# double_amp.net
KiCad netlist of a schematic drawn in Altium Designer
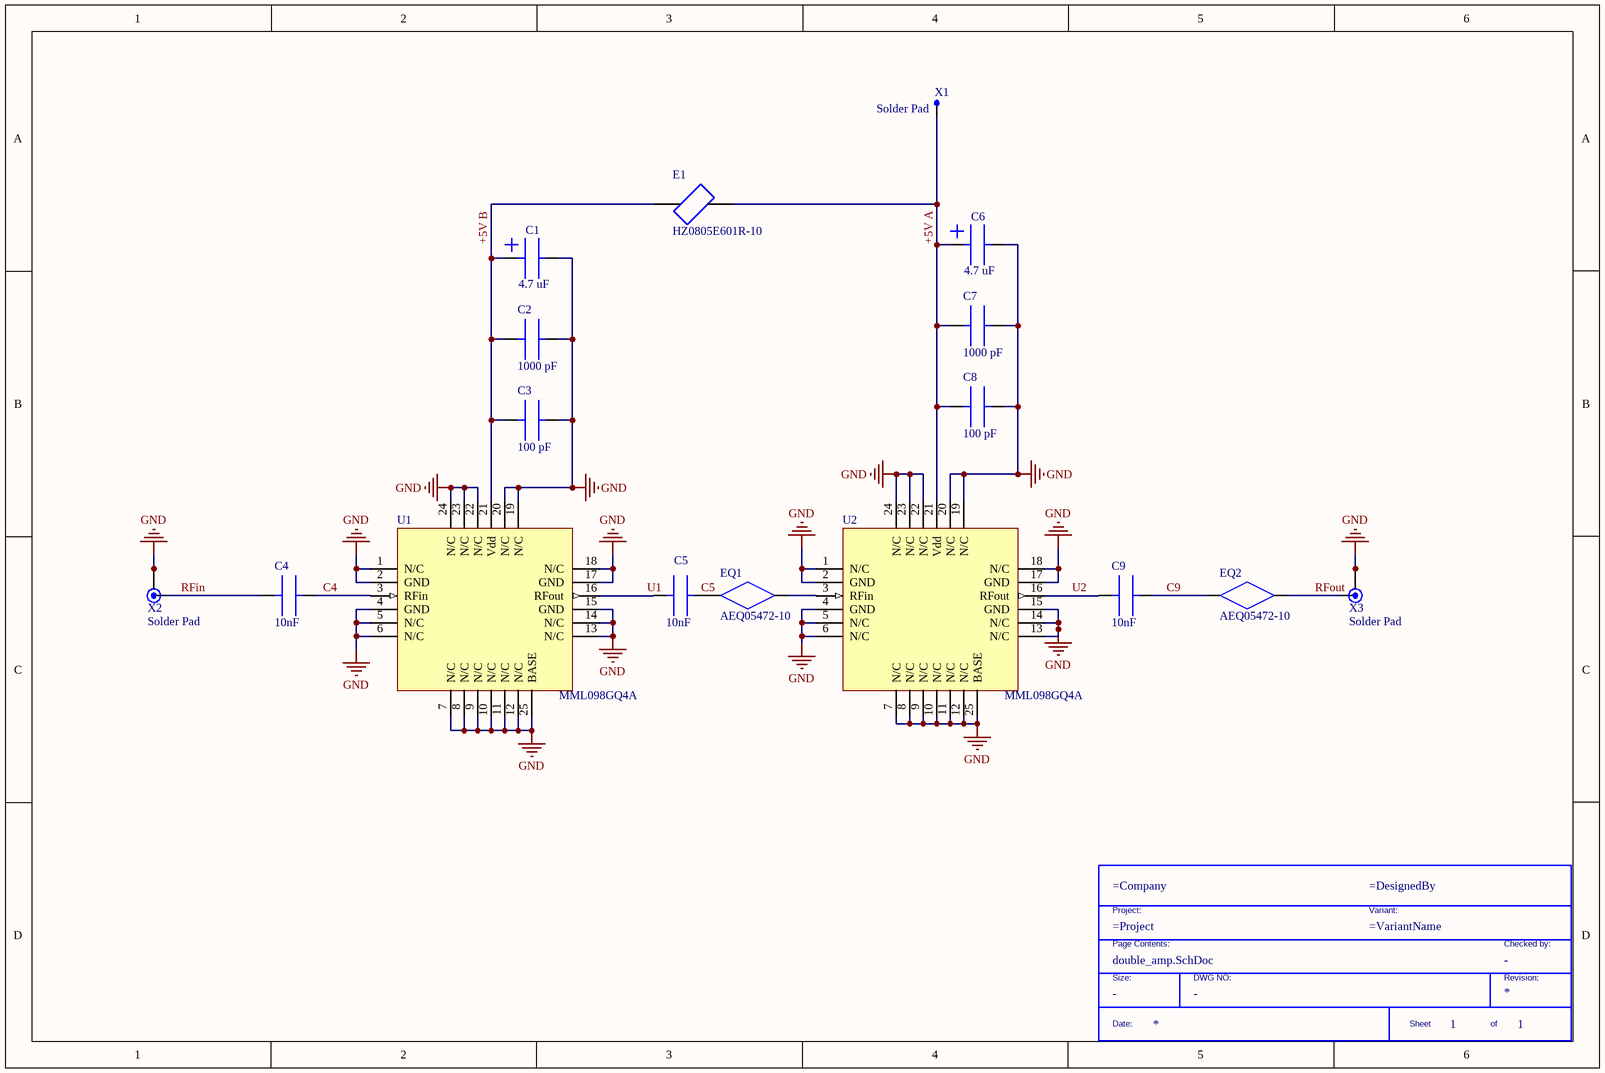
[diagram p0: double_amp.SchDoc]

(export (version "E")
  (design (tool "Eeschema 10.0.6"))
  (components
    (comp (ref "*")
      (value "TitleBlock")
      (description "Standard Title Block")
      (fields (field (name "DWG NO") "-") (field (name "SIZE") "-") (field (name "CHECKED BY") "-"))
      (libsource (lib "amp") (part "TitleBlock"))
    )
    (comp (ref "C1")
      (value "4.7 uF")
      (footprint "C4_7uF")
      (fields
        (field (name "MANUFACTURER") "Vishay Sprague")
        (field (name "MANUFACTURER PART NUMBER") "TH3A475K010C2900")
      )
      (libsource (lib "amp") (part "C7_4uF_TH3A475K010C2900"))
    )
    (comp (ref "C2")
      (value "1000 pF")
      (footprint "C1000pF__C100nF")
      (fields
        (field (name "MANUFACTURER") "Murata")
        (field (name "MANUFACTURER PART NUMBER") "GCM1885C1H102FA16D")
      )
      (libsource (lib "amp") (part "C1000pF_GCM1885C1H102FA16D"))
    )
    (comp (ref "C3")
      (value "100 pF")
      (footprint "C100pF")
      (description "Multilayer Ceramic Capacitors MLCC - SMD/SMT 100 pF 100 VDC 1% 0402 C0G (NP0)")
      (fields
        (field (name "MANUFACTURER") "Murata")
        (field (name "MANUFACTURER PART NUMBER") "GRM1555C2A101FA01D")
      )
      (libsource (lib "amp") (part "C100pF_GRM1555C2A101FA01D"))
    )
    (comp (ref "C4")
      (value "10nF")
      (footprint "C10nF")
      (fields (field (name "MANUFACTURER") "Murata") (field (name "MANUFACTURER PART NUMBER") "939113733510"))
      (libsource (lib "amp") (part "C10nF_939113733510"))
    )
    (comp (ref "C5")
      (value "10nF")
      (footprint "C10nF")
      (fields (field (name "MANUFACTURER") "Murata") (field (name "MANUFACTURER PART NUMBER") "939113733510"))
      (libsource (lib "amp") (part "C10nF_939113733510"))
    )
    (comp (ref "C6")
      (value "4.7 uF")
      (footprint "C4_7uF")
      (fields
        (field (name "MANUFACTURER") "Vishay Sprague")
        (field (name "MANUFACTURER PART NUMBER") "TH3A475K010C2900")
      )
      (libsource (lib "amp") (part "C7_4uF_TH3A475K010C2900"))
    )
    (comp (ref "C7")
      (value "1000 pF")
      (footprint "C1000pF__C100nF")
      (fields
        (field (name "MANUFACTURER") "Murata")
        (field (name "MANUFACTURER PART NUMBER") "GCM1885C1H102FA16D")
      )
      (libsource (lib "amp") (part "C1000pF_GCM1885C1H102FA16D"))
    )
    (comp (ref "C8")
      (value "100 pF")
      (footprint "C100pF")
      (description "Multilayer Ceramic Capacitors MLCC - SMD/SMT 100 pF 100 VDC 1% 0402 C0G (NP0)")
      (fields
        (field (name "MANUFACTURER") "Murata")
        (field (name "MANUFACTURER PART NUMBER") "GRM1555C2A101FA01D")
      )
      (libsource (lib "amp") (part "C100pF_GRM1555C2A101FA01D"))
    )
    (comp (ref "C9")
      (value "10nF")
      (footprint "C10nF")
      (fields (field (name "MANUFACTURER") "Murata") (field (name "MANUFACTURER PART NUMBER") "939113733510"))
      (libsource (lib "amp") (part "C10nF_939113733510"))
    )
    (comp (ref "E1")
      (value "HZ0805E601R-10")
      (footprint "FB_HZ0805E601R-10")
      (fields (field (name "MF") "Laird-Signal Integrity Products"))
      (libsource (lib "HZ0805E601R-10") (part "HZ0805E601R-10"))
    )
    (comp (ref "EQ1")
      (value "AEQ05472-10")
      (footprint "EQ_AEQ05472")
      (description "Rf Filter Gain Equalizer 2SMD")
      (fields (field (name "MANUFACTURER") "Knowles Dielectric Labs"))
      (libsource (lib "amp") (part "EQ_AEQ05472-10"))
    )
    (comp (ref "EQ2")
      (value "AEQ05472-10")
      (footprint "EQ_AEQ05472")
      (description "Rf Filter Gain Equalizer 2SMD")
      (fields (field (name "MANUFACTURER") "Knowles Dielectric Labs"))
      (libsource (lib "amp") (part "EQ_AEQ05472-10"))
    )
    (comp (ref "U1")
      (value "MML098GQ4A")
      (footprint "amp_MML098GQ4A")
      (libsource (lib "amp") (part "amp_MML098GQ4A"))
    )
    (comp (ref "U2")
      (value "MML098GQ4A")
      (footprint "amp_MML098GQ4A")
      (libsource (lib "amp") (part "amp_MML098GQ4A"))
    )
    (comp (ref "X1")
      (value "Solder Pad")
      (footprint "Solder Pad")
      (description "Pad to solder wires to")
      (libsource (lib "amp") (part "Solder Pad"))
    )
    (comp (ref "X2")
      (value "Solder Pad")
      (footprint "CPW Edge Connector")
      (description "Solder pad for RF Coplanar Waveguide Rogers 4350B Thickness 0.020\" Copper 1oz")
      (libsource (lib "amp") (part "RF  CPW Solder Pad"))
    )
    (comp (ref "X3")
      (value "Solder Pad")
      (footprint "CPW Edge Connector")
      (description "Solder pad for RF Coplanar Waveguide Rogers 4350B Thickness 0.020\" Copper 1oz")
      (libsource (lib "amp") (part "RF  CPW Solder Pad"))
    )
  )
  (nets
    (net (code "1") (name "/+5V A") (class "Default")
      (node (ref "C6") (pin "1") (pinfunction "+_1") (pintype "passive"))
      (node (ref "C7") (pin "1") (pinfunction "1_1") (pintype "passive"))
      (node (ref "C8") (pin "1") (pinfunction "1_1") (pintype "passive"))
      (node (ref "E1") (pin "2") (pinfunction "2_2") (pintype "passive"))
      (node (ref "U2") (pin "21") (pinfunction "Vdd_21") (pintype "power_in"))
      (node (ref "X1") (pin "1") (pinfunction "1_1") (pintype "passive"))
    )
    (net (code "2") (name "/+5V B") (class "Default")
      (node (ref "C1") (pin "1") (pinfunction "+_1") (pintype "passive"))
      (node (ref "C2") (pin "1") (pinfunction "1_1") (pintype "passive"))
      (node (ref "C3") (pin "1") (pinfunction "1_1") (pintype "passive"))
      (node (ref "E1") (pin "1") (pinfunction "1_1") (pintype "passive"))
      (node (ref "U1") (pin "21") (pinfunction "Vdd_21") (pintype "power_in"))
    )
    (net (code "3") (name "/C4") (class "Default")
      (node (ref "C4") (pin "2") (pinfunction "2_2") (pintype "passive"))
      (node (ref "U1") (pin "3") (pinfunction "RFin_3") (pintype "input"))
    )
    (net (code "5") (name "/C9") (class "Default")
      (node (ref "C9") (pin "2") (pinfunction "2_2") (pintype "passive"))
      (node (ref "EQ2") (pin "1") (pinfunction "1_1") (pintype "passive"))
    )
    (net (code "6") (name "/RFin") (class "Default")
      (node (ref "C4") (pin "1") (pinfunction "1_1") (pintype "passive"))
      (node (ref "X2") (pin "1") (pinfunction "1_1") (pintype "passive"))
    )
    (net (code "7") (name "/RFout") (class "Default")
      (node (ref "EQ2") (pin "2") (pinfunction "2_2") (pintype "passive"))
      (node (ref "X3") (pin "1") (pinfunction "1_1") (pintype "passive"))
    )
    (net (code "10") (name "/U1") (class "Default")
      (node (ref "C5") (pin "1") (pinfunction "1_1") (pintype "passive"))
      (node (ref "U1") (pin "16") (pinfunction "RFout_16") (pintype "output"))
    )
    (net (code "11") (name "/U2") (class "Default")
      (node (ref "C9") (pin "1") (pinfunction "1_1") (pintype "passive"))
      (node (ref "U2") (pin "16") (pinfunction "RFout_16") (pintype "output"))
    )
    (net (code "12") (name "GND") (class "Default")
      (node (ref "C1") (pin "2") (pinfunction "2_2") (pintype "passive"))
      (node (ref "C2") (pin "2") (pinfunction "2_2") (pintype "passive"))
      (node (ref "C3") (pin "2") (pinfunction "2_2") (pintype "passive"))
      (node (ref "C6") (pin "2") (pinfunction "2_2") (pintype "passive"))
      (node (ref "C7") (pin "2") (pinfunction "2_2") (pintype "passive"))
      (node (ref "C8") (pin "2") (pinfunction "2_2") (pintype "passive"))
      (node (ref "U1") (pin "1") (pinfunction "N/C_1") (pintype "passive"))
      (node (ref "U1") (pin "10") (pinfunction "N/C_10") (pintype "passive"))
      (node (ref "U1") (pin "11") (pinfunction "N/C_11") (pintype "passive"))
      (node (ref "U1") (pin "12") (pinfunction "N/C_12") (pintype "passive"))
      (node (ref "U1") (pin "13") (pinfunction "N/C_13") (pintype "passive"))
      (node (ref "U1") (pin "14") (pinfunction "N/C_14") (pintype "passive"))
      (node (ref "U1") (pin "15") (pinfunction "GND_15") (pintype "power_in"))
      (node (ref "U1") (pin "17") (pinfunction "GND_17") (pintype "power_in"))
      (node (ref "U1") (pin "18") (pinfunction "N/C_18") (pintype "passive"))
      (node (ref "U1") (pin "19") (pinfunction "N/C_19") (pintype "passive"))
      (node (ref "U1") (pin "2") (pinfunction "GND_2") (pintype "power_in"))
      (node (ref "U1") (pin "20") (pinfunction "N/C_20") (pintype "passive"))
      (node (ref "U1") (pin "22") (pinfunction "N/C_22") (pintype "passive"))
      (node (ref "U1") (pin "23") (pinfunction "N/C_23") (pintype "passive"))
      (node (ref "U1") (pin "24") (pinfunction "N/C_24") (pintype "passive"))
      (node (ref "U1") (pin "25") (pinfunction "BASE_25") (pintype "power_in"))
      (node (ref "U1") (pin "4") (pinfunction "GND_4") (pintype "power_in"))
      (node (ref "U1") (pin "5") (pinfunction "N/C_5") (pintype "passive"))
      (node (ref "U1") (pin "6") (pinfunction "N/C_6") (pintype "passive"))
      (node (ref "U1") (pin "7") (pinfunction "N/C_7") (pintype "passive"))
      (node (ref "U1") (pin "8") (pinfunction "N/C_8") (pintype "passive"))
      (node (ref "U1") (pin "9") (pinfunction "N/C_9") (pintype "passive"))
      (node (ref "U2") (pin "1") (pinfunction "N/C_1") (pintype "passive"))
      (node (ref "U2") (pin "10") (pinfunction "N/C_10") (pintype "passive"))
      (node (ref "U2") (pin "11") (pinfunction "N/C_11") (pintype "passive"))
      (node (ref "U2") (pin "12") (pinfunction "N/C_12") (pintype "passive"))
      (node (ref "U2") (pin "13") (pinfunction "N/C_13") (pintype "passive"))
      (node (ref "U2") (pin "14") (pinfunction "N/C_14") (pintype "passive"))
      (node (ref "U2") (pin "15") (pinfunction "GND_15") (pintype "power_in"))
      (node (ref "U2") (pin "17") (pinfunction "GND_17") (pintype "power_in"))
      (node (ref "U2") (pin "18") (pinfunction "N/C_18") (pintype "passive"))
      (node (ref "U2") (pin "19") (pinfunction "N/C_19") (pintype "passive"))
      (node (ref "U2") (pin "2") (pinfunction "GND_2") (pintype "power_in"))
      (node (ref "U2") (pin "20") (pinfunction "N/C_20") (pintype "passive"))
      (node (ref "U2") (pin "22") (pinfunction "N/C_22") (pintype "passive"))
      (node (ref "U2") (pin "23") (pinfunction "N/C_23") (pintype "passive"))
      (node (ref "U2") (pin "24") (pinfunction "N/C_24") (pintype "passive"))
      (node (ref "U2") (pin "25") (pinfunction "BASE_25") (pintype "power_in"))
      (node (ref "U2") (pin "4") (pinfunction "GND_4") (pintype "power_in"))
      (node (ref "U2") (pin "5") (pinfunction "N/C_5") (pintype "passive"))
      (node (ref "U2") (pin "6") (pinfunction "N/C_6") (pintype "passive"))
      (node (ref "U2") (pin "7") (pinfunction "N/C_7") (pintype "passive"))
      (node (ref "U2") (pin "8") (pinfunction "N/C_8") (pintype "passive"))
      (node (ref "U2") (pin "9") (pinfunction "N/C_9") (pintype "passive"))
      (node (ref "X2") (pin "2") (pinfunction "2_2") (pintype "passive"))
      (node (ref "X2") (pin "3") (pinfunction "3_3") (pintype "passive"))
      (node (ref "X3") (pin "2") (pinfunction "2_2") (pintype "passive"))
      (node (ref "X3") (pin "3") (pinfunction "3_3") (pintype "passive"))
    )
    (net (code "13") (name "Net-(C5-Pad2)") (class "Default")
      (node (ref "C5") (pin "2") (pinfunction "2_2") (pintype "passive"))
      (node (ref "EQ1") (pin "1") (pinfunction "1_1") (pintype "passive"))
    )
    (net (code "14") (name "Net-(U2-RFin)") (class "Default")
      (node (ref "EQ1") (pin "2") (pinfunction "2_2") (pintype "passive"))
      (node (ref "U2") (pin "3") (pinfunction "RFin_3") (pintype "input"))
    )
  )
)
